# schematic_file.net
KiCad netlist of a schematic drawn in EAGLE
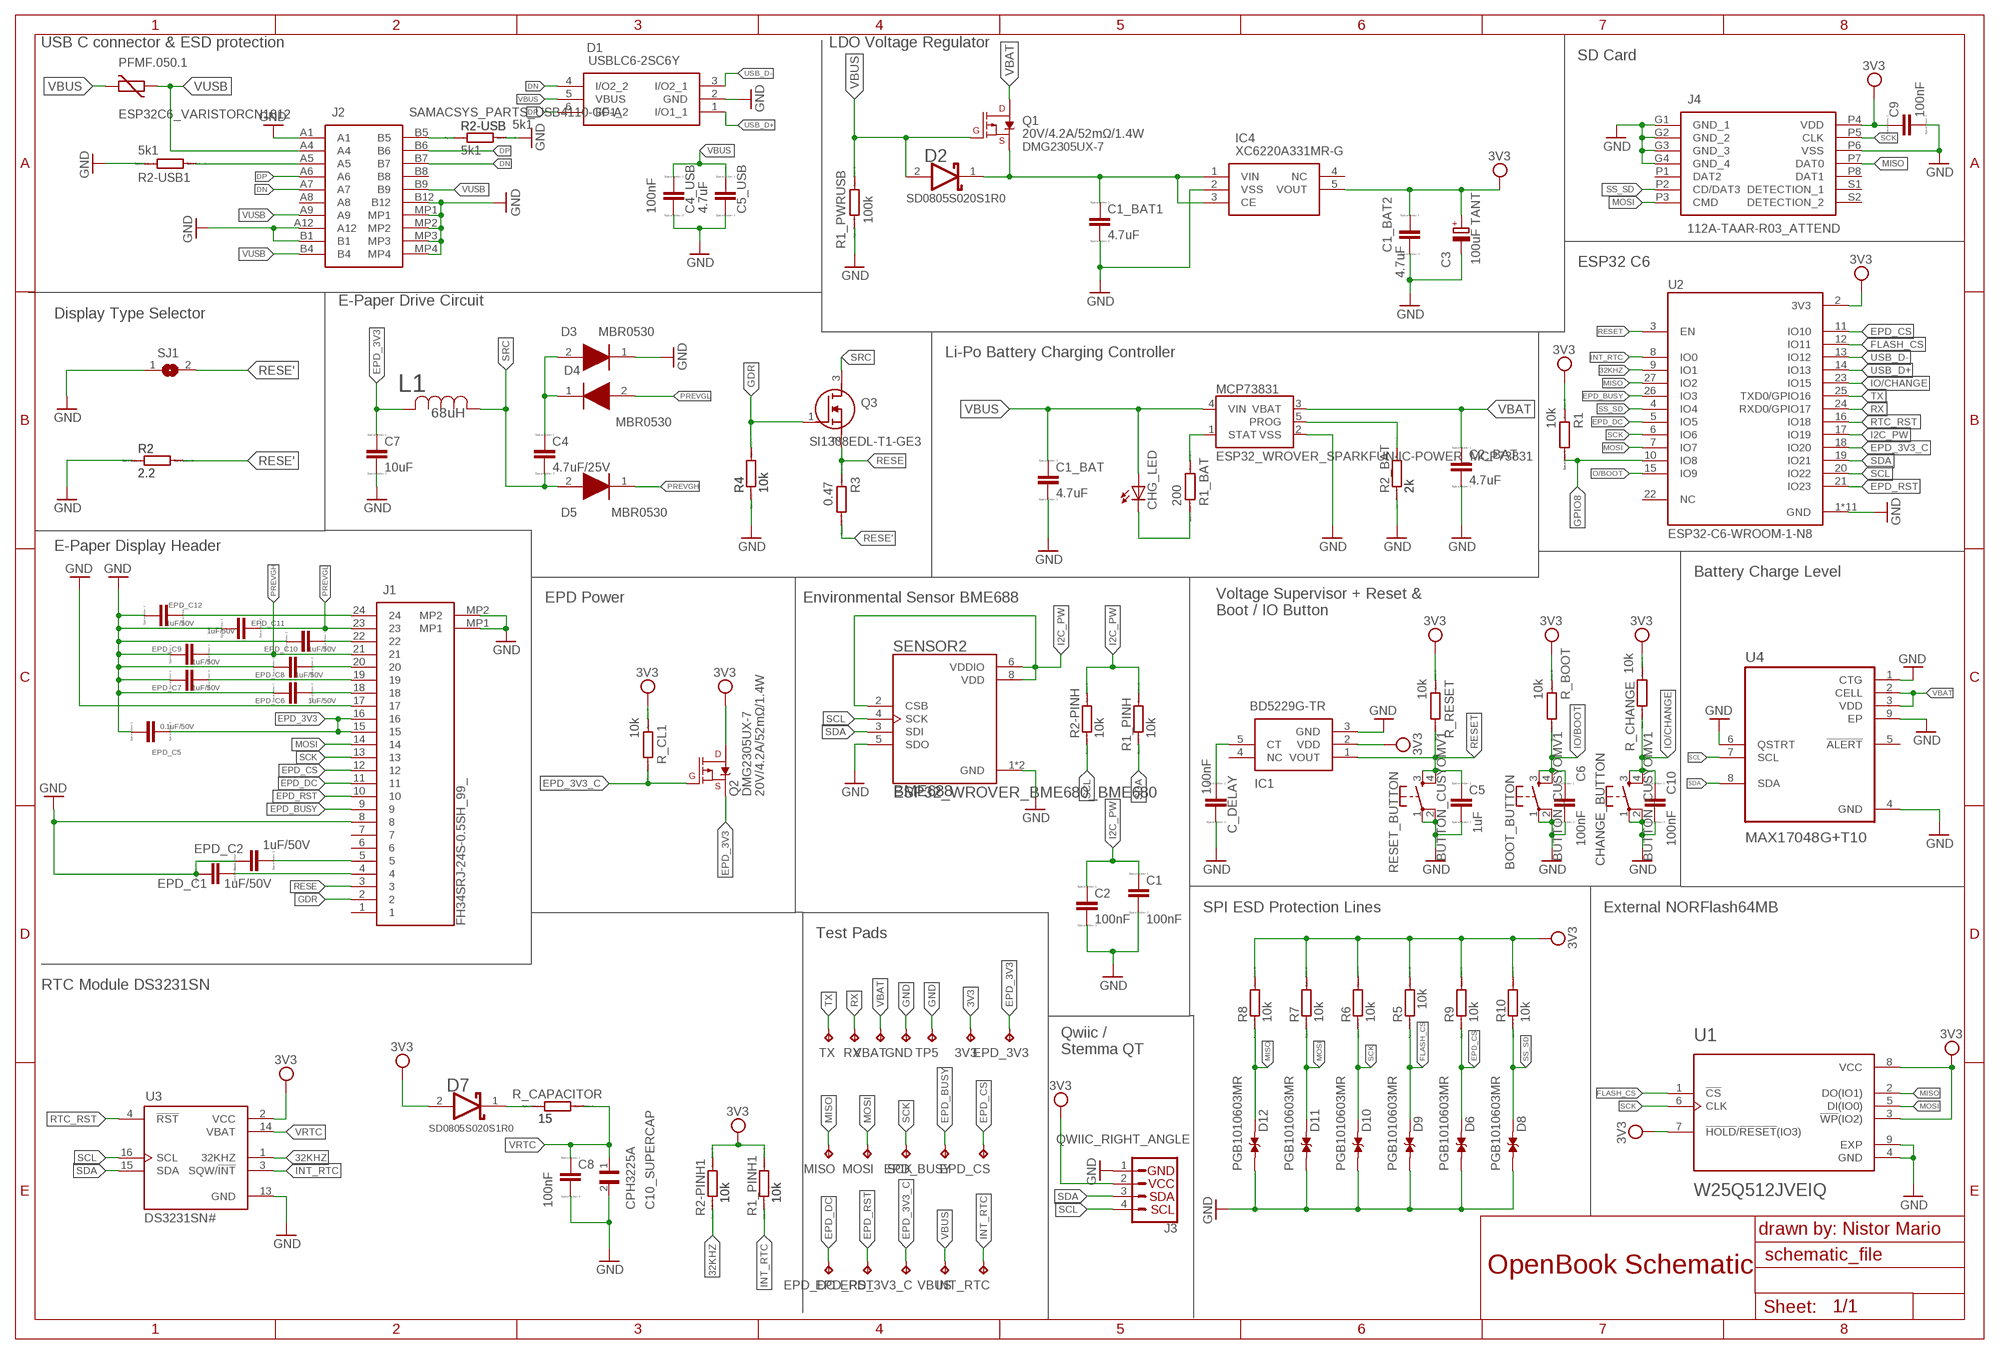
[diagram p0: schematic, sheet 1]

(export (version "E")
  (design (tool "Eeschema 10.0.6"))
  (components
    (comp (ref "3V3")
      (value "TPTP20R")
      (footprint "eagle-import:TP20R")
      (libsource (lib "eagle-import") (part "TPTP20R"))
    )
    (comp (ref "BOOT_BUTTON")
      (value "BUTTON_CUSYOMV1")
      (footprint "eagle-import:MYBUTTON")
      (libsource (lib "eagle-import") (part "BUTTON_CUSYOMV1"))
    )
    (comp (ref "C1")
      (value "100nF")
      (footprint "eagle-import:EAGLE-LTSPICE_C0402")
      (libsource (lib "eagle-import") (part "EAGLE-LTSPICE_CC0402"))
    )
    (comp (ref "C1_BAT")
      (value "4.7uF")
      (footprint "eagle-import:ESP32_WROVER_EAGLE-LTSPICE_C0402")
      (libsource (lib "eagle-import") (part "ESP32_WROVER_EAGLE-LTSPICE_CC0402"))
    )
    (comp (ref "C1_BAT1")
      (value "4.7uF")
      (footprint "eagle-import:EAGLE-LTSPICE_C0402")
      (libsource (lib "eagle-import") (part "EAGLE-LTSPICE_CC0402"))
    )
    (comp (ref "C1_BAT2")
      (value "4.7uF")
      (footprint "eagle-import:ESP32_WROVER_EAGLE-LTSPICE_C0402")
      (libsource (lib "eagle-import") (part "ESP32_WROVER_EAGLE-LTSPICE_CC0402"))
    )
    (comp (ref "C2")
      (value "100nF")
      (footprint "eagle-import:EAGLE-LTSPICE_C0402")
      (libsource (lib "eagle-import") (part "EAGLE-LTSPICE_CC0402"))
    )
    (comp (ref "C2_BAT")
      (value "4.7uF")
      (footprint "eagle-import:EAGLE-LTSPICE_C0402")
      (libsource (lib "eagle-import") (part "EAGLE-LTSPICE_CC0402"))
    )
    (comp (ref "C3")
      (value "100uF TANT")
      (footprint "eagle-import:RCL_CT3528")
      (libsource (lib "eagle-import") (part "RCL_CPOL-EUCT3528"))
    )
    (comp (ref "C4")
      (value "4.7uF/25V")
      (footprint "eagle-import:EAGLE-LTSPICE_C0402")
      (libsource (lib "eagle-import") (part "EAGLE-LTSPICE_CC0402"))
    )
    (comp (ref "C4_USB")
      (value "100nF")
      (footprint "eagle-import:ESP32_WROVER_EAGLE-LTSPICE_C0402")
      (libsource (lib "eagle-import") (part "ESP32_WROVER_EAGLE-LTSPICE_CC0402"))
    )
    (comp (ref "C5")
      (value "1uF")
      (footprint "eagle-import:EAGLE-LTSPICE_C0402")
      (libsource (lib "eagle-import") (part "EAGLE-LTSPICE_CC0402"))
    )
    (comp (ref "C5_USB")
      (value "4.7uF")
      (footprint "eagle-import:ESP32_WROVER_EAGLE-LTSPICE_C0402")
      (libsource (lib "eagle-import") (part "ESP32_WROVER_EAGLE-LTSPICE_CC0402"))
    )
    (comp (ref "C6")
      (value "100nF")
      (footprint "eagle-import:ESP32_WROVER_EAGLE-LTSPICE_C0402")
      (libsource (lib "eagle-import") (part "ESP32_WROVER_EAGLE-LTSPICE_CC0402"))
    )
    (comp (ref "C7")
      (value "10uF")
      (footprint "eagle-import:EAGLE-LTSPICE_C0402")
      (libsource (lib "eagle-import") (part "EAGLE-LTSPICE_CC0402"))
    )
    (comp (ref "C8")
      (value "100nF")
      (footprint "eagle-import:EAGLE-LTSPICE_C0402")
      (libsource (lib "eagle-import") (part "EAGLE-LTSPICE_CC0402"))
    )
    (comp (ref "C9")
      (value "100nF")
      (footprint "eagle-import:EAGLE-LTSPICE_C0402")
      (libsource (lib "eagle-import") (part "EAGLE-LTSPICE_CC0402"))
    )
    (comp (ref "C10")
      (value "100nF")
      (footprint "eagle-import:ESP32_WROVER_EAGLE-LTSPICE_C0402")
      (libsource (lib "eagle-import") (part "ESP32_WROVER_EAGLE-LTSPICE_CC0402"))
    )
    (comp (ref "C10_SUPERCAP")
      (value "CPH3225A")
      (footprint "eagle-import:CAPCP3225X100N")
      (fields (field (name "MF") "Seiko Instruments"))
      (libsource (lib "eagle-import") (part "CPH3225A"))
    )
    (comp (ref "CHANGE_BUTTON")
      (value "BUTTON_CUSYOMV1")
      (footprint "eagle-import:MYBUTTON")
      (libsource (lib "eagle-import") (part "BUTTON_CUSYOMV1"))
    )
    (comp (ref "CHG_LED")
      (value "ADAFRUIT_LEDCHIP-LED0603")
      (footprint "eagle-import:ADAFRUIT_CHIP-LED0603")
      (libsource (lib "eagle-import") (part "ADAFRUIT_LEDCHIP-LED0603"))
    )
    (comp (ref "C_DELAY")
      (value "100nF")
      (footprint "eagle-import:EAGLE-LTSPICE_C0402")
      (libsource (lib "eagle-import") (part "EAGLE-LTSPICE_CC0402"))
    )
    (comp (ref "D1")
      (value "USBLC6-2SC6Y")
      (footprint "eagle-import:SOT95P280X145-6N")
      (fields (field (name "MF") "STMicroelectronics"))
      (libsource (lib "eagle-import") (part "USBLC6-2SC6Y"))
    )
    (comp (ref "D2")
      (value "ESP32_WROVER_AVX---SD0805S020S1R0_AVX_SD0805S020S1R0_0_0AVX_SD0805S020S1R0_0_0")
      (footprint "eagle-import:ESP32_WROVER_AVX---SD0805S020S1R0_AVX_SD0805S020S1R0_0")
      (fields
        (field (name "DIGIKEY_PART_NUMBER") "478-7800-1-ND")
        (field (name "MF") "AVX")
        (field (name "MOUSER_PART_NUMBER") "581-SD0805S020S1R0")
      )
      (libsource (lib "eagle-import") (part "ESP32_WROVER_AVX---SD0805S020S1R0_AVX_SD0805S020S1R0_0_0AVX_SD0805S020S1R0_0_0"))
    )
    (comp (ref "D3")
      (value "MBR0530")
      (footprint "eagle-import:SOD3716X135N")
      (fields (field (name "MF") "ON Semiconductor"))
      (libsource (lib "eagle-import") (part "MBR0530"))
    )
    (comp (ref "D4")
      (value "MBR0530")
      (footprint "eagle-import:SOD3716X135N")
      (fields (field (name "MF") "ON Semiconductor"))
      (libsource (lib "eagle-import") (part "MBR0530"))
    )
    (comp (ref "D5")
      (value "MBR0530")
      (footprint "eagle-import:SOD3716X135N")
      (fields (field (name "MF") "ON Semiconductor"))
      (libsource (lib "eagle-import") (part "MBR0530"))
    )
    (comp (ref "D6")
      (value "PGB1010603MR")
      (footprint "eagle-import:DIOC1608X36N")
      (fields (field (name "MF") "Littelfuse Inc."))
      (libsource (lib "eagle-import") (part "PGB1010603MR"))
    )
    (comp (ref "D7")
      (value "ESP32_WROVER_AVX---SD0805S020S1R0_AVX_SD0805S020S1R0_0_0AVX_SD0805S020S1R0_0_0")
      (footprint "eagle-import:ESP32_WROVER_AVX---SD0805S020S1R0_AVX_SD0805S020S1R0_0")
      (fields
        (field (name "DIGIKEY_PART_NUMBER") "478-7800-1-ND")
        (field (name "MF") "AVX")
        (field (name "MOUSER_PART_NUMBER") "581-SD0805S020S1R0")
      )
      (libsource (lib "eagle-import") (part "ESP32_WROVER_AVX---SD0805S020S1R0_AVX_SD0805S020S1R0_0_0AVX_SD0805S020S1R0_0_0"))
    )
    (comp (ref "D8")
      (value "PGB1010603MR")
      (footprint "eagle-import:DIOC1608X36N")
      (fields (field (name "MF") "Littelfuse Inc."))
      (libsource (lib "eagle-import") (part "PGB1010603MR"))
    )
    (comp (ref "D9")
      (value "PGB1010603MR")
      (footprint "eagle-import:DIOC1608X36N")
      (fields (field (name "MF") "Littelfuse Inc."))
      (libsource (lib "eagle-import") (part "PGB1010603MR"))
    )
    (comp (ref "D10")
      (value "PGB1010603MR")
      (footprint "eagle-import:DIOC1608X36N")
      (fields (field (name "MF") "Littelfuse Inc."))
      (libsource (lib "eagle-import") (part "PGB1010603MR"))
    )
    (comp (ref "D11")
      (value "PGB1010603MR")
      (footprint "eagle-import:DIOC1608X36N")
      (fields (field (name "MF") "Littelfuse Inc."))
      (libsource (lib "eagle-import") (part "PGB1010603MR"))
    )
    (comp (ref "D12")
      (value "PGB1010603MR")
      (footprint "eagle-import:DIOC1608X36N")
      (fields (field (name "MF") "Littelfuse Inc."))
      (libsource (lib "eagle-import") (part "PGB1010603MR"))
    )
    (comp (ref "EPD_3V3")
      (value "TPTP20R")
      (footprint "eagle-import:TP20R")
      (libsource (lib "eagle-import") (part "TPTP20R"))
    )
    (comp (ref "EPD_3V3_C")
      (value "TPTP20R")
      (footprint "eagle-import:TP20R")
      (libsource (lib "eagle-import") (part "TPTP20R"))
    )
    (comp (ref "EPD_BUSY")
      (value "TPTP20R")
      (footprint "eagle-import:TP20R")
      (libsource (lib "eagle-import") (part "TPTP20R"))
    )
    (comp (ref "EPD_C1")
      (value "1uF/50V")
      (footprint "eagle-import:ESP32_WROVER_EAGLE-LTSPICE_C0402")
      (libsource (lib "eagle-import") (part "ESP32_WROVER_EAGLE-LTSPICE_CC0402"))
    )
    (comp (ref "EPD_C2")
      (value "1uF/50V")
      (footprint "eagle-import:ESP32_WROVER_EAGLE-LTSPICE_C0402")
      (libsource (lib "eagle-import") (part "ESP32_WROVER_EAGLE-LTSPICE_CC0402"))
    )
    (comp (ref "EPD_C5")
      (value "0.1uF/50V")
      (footprint "eagle-import:ESP32_WROVER_EAGLE-LTSPICE_C0402")
      (libsource (lib "eagle-import") (part "ESP32_WROVER_EAGLE-LTSPICE_CC0402"))
    )
    (comp (ref "EPD_C6")
      (value "1uF/50V")
      (footprint "eagle-import:ESP32_WROVER_EAGLE-LTSPICE_C0402")
      (libsource (lib "eagle-import") (part "ESP32_WROVER_EAGLE-LTSPICE_CC0402"))
    )
    (comp (ref "EPD_C7")
      (value "1uF/50V")
      (footprint "eagle-import:ESP32_WROVER_EAGLE-LTSPICE_C0402")
      (libsource (lib "eagle-import") (part "ESP32_WROVER_EAGLE-LTSPICE_CC0402"))
    )
    (comp (ref "EPD_C8")
      (value "1uF/50V")
      (footprint "eagle-import:ESP32_WROVER_EAGLE-LTSPICE_C0402")
      (libsource (lib "eagle-import") (part "ESP32_WROVER_EAGLE-LTSPICE_CC0402"))
    )
    (comp (ref "EPD_C9")
      (value "1uF/50V")
      (footprint "eagle-import:ESP32_WROVER_EAGLE-LTSPICE_C0402")
      (libsource (lib "eagle-import") (part "ESP32_WROVER_EAGLE-LTSPICE_CC0402"))
    )
    (comp (ref "EPD_C10")
      (value "1uF/50V")
      (footprint "eagle-import:ESP32_WROVER_EAGLE-LTSPICE_C0402")
      (libsource (lib "eagle-import") (part "ESP32_WROVER_EAGLE-LTSPICE_CC0402"))
    )
    (comp (ref "EPD_C11")
      (value "1uF/50V")
      (footprint "eagle-import:ESP32_WROVER_EAGLE-LTSPICE_C0402")
      (libsource (lib "eagle-import") (part "ESP32_WROVER_EAGLE-LTSPICE_CC0402"))
    )
    (comp (ref "EPD_C12")
      (value "1uF/50V")
      (footprint "eagle-import:ESP32_WROVER_EAGLE-LTSPICE_C0402")
      (libsource (lib "eagle-import") (part "ESP32_WROVER_EAGLE-LTSPICE_CC0402"))
    )
    (comp (ref "EPD_CS")
      (value "TPTP20R")
      (footprint "eagle-import:TP20R")
      (libsource (lib "eagle-import") (part "TPTP20R"))
    )
    (comp (ref "EPD_DC")
      (value "TPTP20R")
      (footprint "eagle-import:TP20R")
      (libsource (lib "eagle-import") (part "TPTP20R"))
    )
    (comp (ref "EPD_RST")
      (value "TPTP20R")
      (footprint "eagle-import:TP20R")
      (libsource (lib "eagle-import") (part "TPTP20R"))
    )
    (comp (ref "GND")
      (value "TPTP20R")
      (footprint "eagle-import:TP20R")
      (libsource (lib "eagle-import") (part "TPTP20R"))
    )
    (comp (ref "IC1")
      (value "BD5229G-TR")
      (footprint "eagle-import:SOT95P280X125-5N")
      (fields (field (name "MOUSER_PART_NUMBER") "755-BD5229G-TR"))
      (libsource (lib "eagle-import") (part "BD5229G-TR"))
    )
    (comp (ref "IC4")
      (value "XC6220A331MR-G")
      (footprint "eagle-import:SOT95P280X120-5N")
      (fields (field (name "MOUSER_PART_NUMBER") "865-XC6220A331MR-G"))
      (libsource (lib "eagle-import") (part "XC6220A331MR-G"))
    )
    (comp (ref "INT_RTC")
      (value "TPTP20R")
      (footprint "eagle-import:TP20R")
      (libsource (lib "eagle-import") (part "TPTP20R"))
    )
    (comp (ref "J1")
      (value "FH34SRJ-24S-0.5SH_99_")
      (footprint "eagle-import:FH34SRJ24S05SH99")
      (fields
        (field (name "MANUFACTURER_PART_NUMBER") "FH34SRJ-24S-0.5SH(99)")
        (field (name "MOUSER_PART_NUMBER") "798-FH34SRJ24S05SH99")
      )
      (libsource (lib "eagle-import") (part "FH34SRJ-24S-0.5SH_99_"))
    )
    (comp (ref "J2")
      (value "SAMACSYS_PARTS_USB4110-GF-A")
      (footprint "eagle-import:SAMACSYS_PARTS_USB4110GFA")
      (fields
        (field (name "MANUFACTURER_PART_NUMBER") "USB4110-GF-A")
        (field (name "MOUSER_PART_NUMBER") "640-USB4110-GF-A")
      )
      (libsource (lib "eagle-import") (part "SAMACSYS_PARTS_USB4110-GF-A"))
    )
    (comp (ref "J3")
      (value "QWIIC_RIGHT_ANGLE")
      (footprint "eagle-import:JST04_1MM_RA")
      (libsource (lib "eagle-import") (part "QWIIC_CONNECTORJS-1MM"))
    )
    (comp (ref "J4")
      (value "112A-TAAR-R03_ATTEND")
      (footprint "eagle-import:112ATAARR03ATTEND")
      (fields (field (name "MANUFACTURER_PART_NUMBER") "112A-TAAR-R03 ATTEND"))
      (libsource (lib "eagle-import") (part "112A-TAAR-R03_ATTEND"))
    )
    (comp (ref "L1")
      (value "68uH")
      (footprint "eagle-import:IND_4828-WE-TPC_WRE")
      (fields
        (field (name "MANUFACTURER_PART_NUMBER") "744043680")
        (field (name "COPYRIGHT") "Copyright (C) 2024 Ultra Librarian. All rights reserved.")
      )
      (libsource (lib "eagle-import") (part "744043680IND_4828-WE-TPC_WRE"))
    )
    (comp (ref "MCP73831")
      (value "ESP32_WROVER_SPARKFUN-IC-POWER_MCP73831")
      (footprint "eagle-import:ESP32_WROVER_SPARKFUN-IC-POWER_SOT23-5")
      (libsource (lib "eagle-import") (part "ESP32_WROVER_SPARKFUN-IC-POWER_MCP73831"))
    )
    (comp (ref "MISO")
      (value "TPTP20R")
      (footprint "eagle-import:TP20R")
      (libsource (lib "eagle-import") (part "TPTP20R"))
    )
    (comp (ref "MOSI")
      (value "TPTP20R")
      (footprint "eagle-import:TP20R")
      (libsource (lib "eagle-import") (part "TPTP20R"))
    )
    (comp (ref "PFMF.050.1")
      (value "ESP32C6_VARISTORCN1812")
      (footprint "eagle-import:ESP32C6_VARISTOR_CT_CN1812")
      (libsource (lib "eagle-import") (part "ESP32C6_VARISTORCN1812"))
    )
    (comp (ref "Q1")
      (value "20V/4.2A/52mΩ/1.4W")
      (footprint "eagle-import:ESP32_WROVER_SPARKFUN-DISCRETESEMI_SOT23-3")
      (libsource (lib "eagle-import") (part "ESP32_WROVER_SPARKFUN-DISCRETESEMI_MOSFET_PCH-DMG2305UX-7"))
    )
    (comp (ref "Q2")
      (value "20V/4.2A/52mΩ/1.4W")
      (footprint "eagle-import:ESP32_WROVER_SPARKFUN-DISCRETESEMI_SOT23-3")
      (libsource (lib "eagle-import") (part "ESP32_WROVER_SPARKFUN-DISCRETESEMI_MOSFET_PCH-DMG2305UX-7"))
    )
    (comp (ref "Q3")
      (value "SI1308EDL-T1-GE3")
      (footprint "eagle-import:SOT65P210X110-3N")
      (fields (field (name "MF") "Vishay Siliconix"))
      (libsource (lib "eagle-import") (part "SI1308EDL-T1-GE3"))
    )
    (comp (ref "R1")
      (value "10k")
      (footprint "eagle-import:ESP32_WROVER_EAGLE-LTSPICE_R0402")
      (libsource (lib "eagle-import") (part "ESP32_WROVER_EAGLE-LTSPICE_RR0402"))
    )
    (comp (ref "R1_BAT")
      (value "200")
      (footprint "eagle-import:ESP32_WROVER_EAGLE-LTSPICE_R0402")
      (libsource (lib "eagle-import") (part "ESP32_WROVER_EAGLE-LTSPICE_RR0402"))
    )
    (comp (ref "R1_PINH")
      (value "10k")
      (footprint "eagle-import:ESP32_WROVER_EAGLE-LTSPICE_R0402")
      (libsource (lib "eagle-import") (part "ESP32_WROVER_EAGLE-LTSPICE_RR0402"))
    )
    (comp (ref "R1_PINH1")
      (value "10k")
      (footprint "eagle-import:ESP32_WROVER_EAGLE-LTSPICE_R0402")
      (libsource (lib "eagle-import") (part "ESP32_WROVER_EAGLE-LTSPICE_RR0402"))
    )
    (comp (ref "R1_PWRUSB")
      (value "100k")
      (footprint "eagle-import:ESP32_WROVER_EAGLE-LTSPICE_R0402")
      (libsource (lib "eagle-import") (part "ESP32_WROVER_EAGLE-LTSPICE_RR0402"))
    )
    (comp (ref "R2")
      (value "2.2")
      (footprint "eagle-import:ESP32_WROVER_EAGLE-LTSPICE_R0402")
      (libsource (lib "eagle-import") (part "ESP32_WROVER_EAGLE-LTSPICE_RR0402"))
    )
    (comp (ref "R2-PINH")
      (value "10k")
      (footprint "eagle-import:ESP32_WROVER_EAGLE-LTSPICE_R0402")
      (libsource (lib "eagle-import") (part "ESP32_WROVER_EAGLE-LTSPICE_RR0402"))
    )
    (comp (ref "R2-PINH1")
      (value "10k")
      (footprint "eagle-import:ESP32_WROVER_EAGLE-LTSPICE_R0402")
      (libsource (lib "eagle-import") (part "ESP32_WROVER_EAGLE-LTSPICE_RR0402"))
    )
    (comp (ref "R2-USB")
      (value "5k1")
      (footprint "eagle-import:ESP32_WROVER_EAGLE-LTSPICE_R0402")
      (libsource (lib "eagle-import") (part "ESP32_WROVER_EAGLE-LTSPICE_RR0402"))
    )
    (comp (ref "R2-USB1")
      (value "5k1")
      (footprint "eagle-import:ESP32_WROVER_EAGLE-LTSPICE_R0402")
      (libsource (lib "eagle-import") (part "ESP32_WROVER_EAGLE-LTSPICE_RR0402"))
    )
    (comp (ref "R2_BAT")
      (value "2k")
      (footprint "eagle-import:ESP32_WROVER_EAGLE-LTSPICE_R0402")
      (libsource (lib "eagle-import") (part "ESP32_WROVER_EAGLE-LTSPICE_RR0402"))
    )
    (comp (ref "R3")
      (value "0.47")
      (footprint "eagle-import:ESP32_WROVER_EAGLE-LTSPICE_R0402")
      (libsource (lib "eagle-import") (part "ESP32_WROVER_EAGLE-LTSPICE_RR0402"))
    )
    (comp (ref "R4")
      (value "10k")
      (footprint "eagle-import:ESP32_WROVER_EAGLE-LTSPICE_R0402")
      (libsource (lib "eagle-import") (part "ESP32_WROVER_EAGLE-LTSPICE_RR0402"))
    )
    (comp (ref "R5")
      (value "10k")
      (footprint "eagle-import:ESP32_WROVER_EAGLE-LTSPICE_R0402")
      (libsource (lib "eagle-import") (part "ESP32_WROVER_EAGLE-LTSPICE_RR0402"))
    )
    (comp (ref "R6")
      (value "10k")
      (footprint "eagle-import:ESP32_WROVER_EAGLE-LTSPICE_R0402")
      (libsource (lib "eagle-import") (part "ESP32_WROVER_EAGLE-LTSPICE_RR0402"))
    )
    (comp (ref "R7")
      (value "10k")
      (footprint "eagle-import:ESP32_WROVER_EAGLE-LTSPICE_R0402")
      (libsource (lib "eagle-import") (part "ESP32_WROVER_EAGLE-LTSPICE_RR0402"))
    )
    (comp (ref "R8")
      (value "10k")
      (footprint "eagle-import:ESP32_WROVER_EAGLE-LTSPICE_R0402")
      (libsource (lib "eagle-import") (part "ESP32_WROVER_EAGLE-LTSPICE_RR0402"))
    )
    (comp (ref "R9")
      (value "10k")
      (footprint "eagle-import:ESP32_WROVER_EAGLE-LTSPICE_R0402")
      (libsource (lib "eagle-import") (part "ESP32_WROVER_EAGLE-LTSPICE_RR0402"))
    )
    (comp (ref "R10")
      (value "10k")
      (footprint "eagle-import:ESP32_WROVER_EAGLE-LTSPICE_R0402")
      (libsource (lib "eagle-import") (part "ESP32_WROVER_EAGLE-LTSPICE_RR0402"))
    )
    (comp (ref "RESET_BUTTON")
      (value "BUTTON_CUSYOMV1")
      (footprint "eagle-import:MYBUTTON")
      (libsource (lib "eagle-import") (part "BUTTON_CUSYOMV1"))
    )
    (comp (ref "RX")
      (value "TPTP20R")
      (footprint "eagle-import:TP20R")
      (libsource (lib "eagle-import") (part "TPTP20R"))
    )
    (comp (ref "R_BOOT")
      (value "10k")
      (footprint "eagle-import:ESP32_WROVER_EAGLE-LTSPICE_R0402")
      (libsource (lib "eagle-import") (part "ESP32_WROVER_EAGLE-LTSPICE_RR0402"))
    )
    (comp (ref "R_CAPACITOR")
      (value "15")
      (footprint "eagle-import:ESP32_WROVER_EAGLE-LTSPICE_R0402")
      (libsource (lib "eagle-import") (part "ESP32_WROVER_EAGLE-LTSPICE_RR0402"))
    )
    (comp (ref "R_CHANGE")
      (value "10k")
      (footprint "eagle-import:ESP32_WROVER_EAGLE-LTSPICE_R0402")
      (libsource (lib "eagle-import") (part "ESP32_WROVER_EAGLE-LTSPICE_RR0402"))
    )
    (comp (ref "R_CL1")
      (value "10k")
      (footprint "eagle-import:ESP32_WROVER_EAGLE-LTSPICE_R0402")
      (libsource (lib "eagle-import") (part "ESP32_WROVER_EAGLE-LTSPICE_RR0402"))
    )
    (comp (ref "R_RESET")
      (value "10k")
      (footprint "eagle-import:ESP32_WROVER_EAGLE-LTSPICE_R0402")
      (libsource (lib "eagle-import") (part "ESP32_WROVER_EAGLE-LTSPICE_RR0402"))
    )
    (comp (ref "SCK")
      (value "TPTP20R")
      (footprint "eagle-import:TP20R")
      (libsource (lib "eagle-import") (part "TPTP20R"))
    )
    (comp (ref "SENSOR2")
      (value "ESP32_WROVER_BME680_BME680")
      (footprint "eagle-import:ESP32_WROVER_BME680_PSON80P300X300X100-8N")
      (fields (field (name "MF") "Bosch Sensortec") (field (name "MP") "BME680"))
      (libsource (lib "eagle-import") (part "ESP32_WROVER_BME680_BME680"))
    )
    (comp (ref "SJ1") (value "SJ") (footprint "eagle-import:SJ") (libsource (lib "eagle-import") (part "SJ")))
    (comp (ref "TP5")
      (value "TPTP20R")
      (footprint "eagle-import:TP20R")
      (libsource (lib "eagle-import") (part "TPTP20R"))
    )
    (comp (ref "TX")
      (value "TPTP20R")
      (footprint "eagle-import:TP20R")
      (libsource (lib "eagle-import") (part "TPTP20R"))
    )
    (comp (ref "U1")
      (value "W25Q512JVEIQ")
      (footprint "eagle-import:SON127P600X800X80-9N")
      (fields (field (name "MF") "Winbond Electronics"))
      (libsource (lib "eagle-import") (part "W25Q512JVEIQ"))
    )
    (comp (ref "U2")
      (value "ESP32-C6-WROOM-1-N8")
      (footprint "eagle-import:XCVR_ESP32-C6-WROOM-1-N8")
      (fields (field (name "MF") "Espressif Systems"))
      (libsource (lib "eagle-import") (part "ESP32-C6-WROOM-1-N8"))
    )
    (comp (ref "U3")
      (value "DS3231SN#")
      (footprint "eagle-import:SOIC127P1032X265-16N")
      (fields (field (name "MF") "Analog Devices"))
      (libsource (lib "eagle-import") (part "DS3231SN#"))
    )
    (comp (ref "U4")
      (value "MAX17048G+T10")
      (footprint "eagle-import:SON50P200X200X80-9N")
      (fields (field (name "MF") "Analog Devices"))
      (libsource (lib "eagle-import") (part "MAX17048G+T10"))
    )
    (comp (ref "VBAT")
      (value "TPTP20R")
      (footprint "eagle-import:TP20R")
      (libsource (lib "eagle-import") (part "TPTP20R"))
    )
    (comp (ref "VBUS")
      (value "TPTP20R")
      (footprint "eagle-import:TP20R")
      (libsource (lib "eagle-import") (part "TPTP20R"))
    )
  )
  (nets
    (net (code "1") (name "3V3") (class "Default")
      (node (ref "3V3") (pin "TP") (pinfunction "TP_TP") (pintype "input"))
      (node (ref "C1_BAT2") (pin "1") (pinfunction "1_1") (pintype "passive"))
      (node (ref "C3") (pin "+") (pinfunction "+_+") (pintype "passive"))
      (node (ref "C9") (pin "1") (pinfunction "1_1") (pintype "passive"))
      (node (ref "D7") (pin "2") (pinfunction "ANODE_2") (pintype "bidirectional"))
      (node (ref "IC1") (pin "2") (pinfunction "VDD_2") (pintype "bidirectional"))
      (node (ref "IC4") (pin "5") (pinfunction "VOUT_5") (pintype "bidirectional"))
      (node (ref "J3") (pin "2") (pinfunction "2_2") (pintype "power_in"))
      (node (ref "J4") (pin "P4") (pinfunction "VDD_P4") (pintype "bidirectional"))
      (node (ref "Q2") (pin "3") (pinfunction "D_3") (pintype "bidirectional"))
      (node (ref "R1") (pin "2") (pinfunction "2_2") (pintype "passive"))
      (node (ref "R10") (pin "2") (pinfunction "2_2") (pintype "passive"))
      (node (ref "R1_PINH1") (pin "2") (pinfunction "2_2") (pintype "passive"))
      (node (ref "R2-PINH1") (pin "2") (pinfunction "2_2") (pintype "passive"))
      (node (ref "R5") (pin "2") (pinfunction "2_2") (pintype "passive"))
      (node (ref "R6") (pin "2") (pinfunction "2_2") (pintype "passive"))
      (node (ref "R7") (pin "2") (pinfunction "2_2") (pintype "passive"))
      (node (ref "R8") (pin "2") (pinfunction "2_2") (pintype "passive"))
      (node (ref "R9") (pin "2") (pinfunction "2_2") (pintype "passive"))
      (node (ref "R_BOOT") (pin "2") (pinfunction "2_2") (pintype "passive"))
      (node (ref "R_CHANGE") (pin "2") (pinfunction "2_2") (pintype "passive"))
      (node (ref "R_CL1") (pin "2") (pinfunction "2_2") (pintype "passive"))
      (node (ref "R_RESET") (pin "2") (pinfunction "2_2") (pintype "passive"))
      (node (ref "U1") (pin "3") (pinfunction "~{WP}(IO2)_3") (pintype "bidirectional"))
      (node (ref "U1") (pin "7") (pinfunction "~{HOLD}/~{RESET}(IO3)_7") (pintype "bidirectional"))
      (node (ref "U1") (pin "8") (pinfunction "VCC_8") (pintype "power_in"))
      (node (ref "U2") (pin "2") (pinfunction "3V3_2") (pintype "power_in"))
      (node (ref "U3") (pin "2") (pinfunction "VCC_2") (pintype "power_in"))
    )
    (net (code "2") (name "32KHZ") (class "Default")
      (node (ref "R2-PINH1") (pin "1") (pinfunction "1_1") (pintype "passive"))
      (node (ref "U2") (pin "9") (pinfunction "IO1_9") (pintype "bidirectional"))
      (node (ref "U3") (pin "1") (pinfunction "32KHZ_1") (pintype "output"))
    )
    (net (code "3") (name "DN") (class "Default")
      (node (ref "D1") (pin "4") (pinfunction "I/O2_2_4") (pintype "bidirectional"))
      (node (ref "J2") (pin "A7") (pinfunction "A7_A7") (pintype "bidirectional"))
      (node (ref "J2") (pin "B7") (pinfunction "B7_B7") (pintype "bidirectional"))
    )
    (net (code "4") (name "DP") (class "Default")
      (node (ref "D1") (pin "6") (pinfunction "I/O1_2_6") (pintype "bidirectional"))
      (node (ref "J2") (pin "A6") (pinfunction "A6_A6") (pintype "bidirectional"))
      (node (ref "J2") (pin "B6") (pinfunction "B6_B6") (pintype "bidirectional"))
    )
    (net (code "5") (name "EPD_3V3") (class "Default")
      (node (ref "C7") (pin "1") (pinfunction "1_1") (pintype "passive"))
      (node (ref "EPD_3V3") (pin "TP") (pinfunction "TP_TP") (pintype "input"))
      (node (ref "EPD_C5") (pin "2") (pinfunction "2_2") (pintype "passive"))
      (node (ref "J1") (pin "15") (pinfunction "15_15") (pintype "bidirectional"))
      (node (ref "J1") (pin "16") (pinfunction "16_16") (pintype "bidirectional"))
      (node (ref "L1") (pin "2") (pinfunction "2_2") (pintype "passive"))
      (node (ref "Q2") (pin "2") (pinfunction "S_2") (pintype "bidirectional"))
    )
    (net (code "6") (name "EPD_3V3_C") (class "Default")
      (node (ref "EPD_3V3_C") (pin "TP") (pinfunction "TP_TP") (pintype "input"))
      (node (ref "Q2") (pin "1") (pinfunction "G_1") (pintype "bidirectional"))
      (node (ref "R_CL1") (pin "1") (pinfunction "1_1") (pintype "passive"))
      (node (ref "U2") (pin "18") (pinfunction "IO20_18") (pintype "bidirectional"))
    )
    (net (code "7") (name "EPD_BUSY") (class "Default")
      (node (ref "EPD_BUSY") (pin "TP") (pinfunction "TP_TP") (pintype "input"))
      (node (ref "J1") (pin "9") (pinfunction "9_9") (pintype "bidirectional"))
      (node (ref "U2") (pin "26") (pinfunction "IO3_26") (pintype "bidirectional"))
    )
    (net (code "8") (name "EPD_CS") (class "Default")
      (node (ref "D6") (pin "2") (pinfunction "2_2") (pintype "passive"))
      (node (ref "EPD_CS") (pin "TP") (pinfunction "TP_TP") (pintype "input"))
      (node (ref "J1") (pin "12") (pinfunction "12_12") (pintype "bidirectional"))
      (node (ref "R9") (pin "1") (pinfunction "1_1") (pintype "passive"))
      (node (ref "U2") (pin "11") (pinfunction "IO10_11") (pintype "bidirectional"))
    )
    (net (code "9") (name "EPD_DC") (class "Default")
      (node (ref "EPD_DC") (pin "TP") (pinfunction "TP_TP") (pintype "input"))
      (node (ref "J1") (pin "11") (pinfunction "11_11") (pintype "bidirectional"))
      (node (ref "U2") (pin "5") (pinfunction "IO5_5") (pintype "bidirectional"))
    )
    (net (code "10") (name "EPD_RST") (class "Default")
      (node (ref "EPD_RST") (pin "TP") (pinfunction "TP_TP") (pintype "input"))
      (node (ref "J1") (pin "10") (pinfunction "10_10") (pintype "bidirectional"))
      (node (ref "U2") (pin "21") (pinfunction "IO23_21") (pintype "bidirectional"))
    )
    (net (code "11") (name "FLASH_CS") (class "Default")
      (node (ref "D9") (pin "2") (pinfunction "2_2") (pintype "passive"))
      (node (ref "R5") (pin "1") (pinfunction "1_1") (pintype "passive"))
      (node (ref "U1") (pin "1") (pinfunction "~{CS}_1") (pintype "input"))
      (node (ref "U2") (pin "12") (pinfunction "IO11_12") (pintype "bidirectional"))
    )
    (net (code "12") (name "GDR") (class "Default")
      (node (ref "J1") (pin "2") (pinfunction "2_2") (pintype "bidirectional"))
      (node (ref "Q3") (pin "1") (pinfunction "G_1") (pintype "bidirectional"))
      (node (ref "R4") (pin "2") (pinfunction "2_2") (pintype "passive"))
    )
    (net (code "13") (name "GND") (class "Default")
      (node (ref "BOOT_BUTTON") (pin "1") (pinfunction "1_1") (pintype "passive"))
      (node (ref "BOOT_BUTTON") (pin "2") (pinfunction "2_2") (pintype "passive"))
      (node (ref "C1") (pin "2") (pinfunction "2_2") (pintype "passive"))
      (node (ref "C10") (pin "2") (pinfunction "2_2") (pintype "passive"))
      (node (ref "C10_SUPERCAP") (pin "2") (pinfunction "2_2") (pintype "passive"))
      (node (ref "C1_BAT") (pin "2") (pinfunction "2_2") (pintype "passive"))
      (node (ref "C1_BAT1") (pin "2") (pinfunction "2_2") (pintype "passive"))
      (node (ref "C1_BAT2") (pin "2") (pinfunction "2_2") (pintype "passive"))
      (node (ref "C2") (pin "2") (pinfunction "2_2") (pintype "passive"))
      (node (ref "C2_BAT") (pin "2") (pinfunction "2_2") (pintype "passive"))
      (node (ref "C3") (pin "-") (pinfunction "-_-") (pintype "passive"))
      (node (ref "C4_USB") (pin "2") (pinfunction "2_2") (pintype "passive"))
      (node (ref "C5") (pin "2") (pinfunction "2_2") (pintype "passive"))
      (node (ref "C5_USB") (pin "2") (pinfunction "2_2") (pintype "passive"))
      (node (ref "C6") (pin "2") (pinfunction "2_2") (pintype "passive"))
      (node (ref "C7") (pin "2") (pinfunction "2_2") (pintype "passive"))
      (node (ref "C8") (pin "2") (pinfunction "2_2") (pintype "passive"))
      (node (ref "C9") (pin "2") (pinfunction "2_2") (pintype "passive"))
      (node (ref "CHANGE_BUTTON") (pin "1") (pinfunction "1_1") (pintype "passive"))
      (node (ref "CHANGE_BUTTON") (pin "2") (pinfunction "2_2") (pintype "passive"))
      (node (ref "C_DELAY") (pin "2") (pinfunction "2_2") (pintype "passive"))
      (node (ref "D1") (pin "2") (pinfunction "GND_2") (pintype "bidirectional"))
      (node (ref "D10") (pin "1") (pinfunction "1_1") (pintype "passive"))
      (node (ref "D11") (pin "1") (pinfunction "1_1") (pintype "passive"))
      (node (ref "D12") (pin "1") (pinfunction "1_1") (pintype "passive"))
      (node (ref "D3") (pin "1") (pinfunction "K_1") (pintype "bidirectional"))
      (node (ref "D6") (pin "1") (pinfunction "1_1") (pintype "passive"))
      (node (ref "D8") (pin "1") (pinfunction "1_1") (pintype "passive"))
      (node (ref "D9") (pin "1") (pinfunction "1_1") (pintype "passive"))
      (node (ref "EPD_C1") (pin "1") (pinfunction "1_1") (pintype "passive"))
      (node (ref "EPD_C10") (pin "1") (pinfunction "1_1") (pintype "passive"))
      (node (ref "EPD_C11") (pin "1") (pinfunction "1_1") (pintype "passive"))
      (node (ref "EPD_C12") (pin "1") (pinfunction "1_1") (pintype "passive"))
      (node (ref "EPD_C2") (pin "1") (pinfunction "1_1") (pintype "passive"))
      (node (ref "EPD_C5") (pin "1") (pinfunction "1_1") (pintype "passive"))
      (node (ref "EPD_C6") (pin "1") (pinfunction "1_1") (pintype "passive"))
      (node (ref "EPD_C7") (pin "1") (pinfunction "1_1") (pintype "passive"))
      (node (ref "EPD_C8") (pin "1") (pinfunction "1_1") (pintype "passive"))
      (node (ref "EPD_C9") (pin "1") (pinfunction "1_1") (pintype "passive"))
      (node (ref "GND") (pin "TP") (pinfunction "TP_TP") (pintype "input"))
      (node (ref "IC1") (pin "3") (pinfunction "GND_3") (pintype "bidirectional"))
      (node (ref "IC4") (pin "2") (pinfunction "VSS_2") (pintype "bidirectional"))
      (node (ref "J1") (pin "17") (pinfunction "17_17") (pintype "bidirectional"))
      (node (ref "J1") (pin "8") (pinfunction "8_8") (pintype "bidirectional"))
      (node (ref "J1") (pin "MP1") (pinfunction "MP1_MP1") (pintype "bidirectional"))
      (node (ref "J1") (pin "MP2") (pinfunction "MP2_MP2") (pintype "bidirectional"))
      (node (ref "J2") (pin "A1") (pinfunction "A1_A1") (pintype "bidirectional"))
      (node (ref "J2") (pin "A12") (pinfunction "A12_A12") (pintype "bidirectional"))
      (node (ref "J2") (pin "B1") (pinfunction "B1_B1") (pintype "bidirectional"))
      (node (ref "J2") (pin "B12") (pinfunction "B12_B12") (pintype "bidirectional"))
      (node (ref "J2") (pin "MP1") (pinfunction "MP1_MP1") (pintype "bidirectional"))
      (node (ref "J2") (pin "MP2") (pinfunction "MP2_MP2") (pintype "bidirectional"))
      (node (ref "J2") (pin "MP3") (pinfunction "MP3_MP3") (pintype "bidirectional"))
      (node (ref "J2") (pin "MP4") (pinfunction "MP4_MP4") (pintype "bidirectional"))
      (node (ref "J3") (pin "1") (pinfunction "1_1") (pintype "power_in"))
      (node (ref "J4") (pin "G1") (pinfunction "GND_1_G1") (pintype "bidirectional"))
      (node (ref "J4") (pin "G2") (pinfunction "GND_2_G2") (pintype "bidirectional"))
      (node (ref "J4") (pin "G3") (pinfunction "GND_3_G3") (pintype "bidirectional"))
      (node (ref "J4") (pin "G4") (pinfunction "GND_4_G4") (pintype "bidirectional"))
      (node (ref "J4") (pin "P6") (pinfunction "VSS_P6") (pintype "bidirectional"))
      (node (ref "MCP73831") (pin "2") (pinfunction "VSS_2") (pintype "power_in"))
      (node (ref "R1_PWRUSB") (pin "2") (pinfunction "2_2") (pintype "passive"))
      (node (ref "R2") (pin "1") (pinfunction "1_1") (pintype "passive"))
      (node (ref "R2-USB") (pin "2") (pinfunction "2_2") (pintype "passive"))
      (node (ref "R2-USB1") (pin "1") (pinfunction "1_1") (pintype "passive"))
      (node (ref "R2_BAT") (pin "1") (pinfunction "1_1") (pintype "passive"))
      (node (ref "R4") (pin "1") (pinfunction "1_1") (pintype "passive"))
      (node (ref "RESET_BUTTON") (pin "1") (pinfunction "1_1") (pintype "passive"))
      (node (ref "RESET_BUTTON") (pin "2") (pinfunction "2_2") (pintype "passive"))
      (node (ref "SENSOR2") (pin "1") (pinfunction "GND_1") (pintype "power_in"))
      (node (ref "SENSOR2") (pin "5") (pinfunction "SDO_5") (pintype "bidirectional"))
      (node (ref "SENSOR2") (pin "7") (pinfunction "GND_7") (pintype "power_in"))
      (node (ref "SJ1") (pin "1") (pinfunction "1_1") (pintype "passive"))
      (node (ref "TP5") (pin "TP") (pinfunction "TP_TP") (pintype "input"))
      (node (ref "U1") (pin "4") (pinfunction "GND_4") (pintype "power_in"))
      (node (ref "U1") (pin "9") (pinfunction "EXP_9") (pintype "passive"))
      (node (ref "U2") (pin "1") (pinfunction "GND_1") (pintype "power_in"))
      (node (ref "U2") (pin "28") (pinfunction "GND_28") (pintype "power_in"))
      (node (ref "U2") (pin "29_1") (pinfunction "GND_29_1") (pintype "power_in"))
      (node (ref "U2") (pin "29_2") (pinfunction "GND_29_2") (pintype "power_in"))
      (node (ref "U2") (pin "29_3") (pinfunction "GND_29_3") (pintype "power_in"))
      (node (ref "U2") (pin "29_4") (pinfunction "GND_29_4") (pintype "power_in"))
      (node (ref "U2") (pin "29_5") (pinfunction "GND_29_5") (pintype "power_in"))
      (node (ref "U2") (pin "29_6") (pinfunction "GND_29_6") (pintype "power_in"))
      (node (ref "U2") (pin "29_7") (pinfunction "GND_29_7") (pintype "power_in"))
      (node (ref "U2") (pin "29_8") (pinfunction "GND_29_8") (pintype "power_in"))
      (node (ref "U2") (pin "29_9") (pinfunction "GND_29_9") (pintype "power_in"))
      (node (ref "U3") (pin "13") (pinfunction "GND_13") (pintype "power_in"))
      (node (ref "U4") (pin "1") (pinfunction "CTG_1") (pintype "power_in"))
      (node (ref "U4") (pin "4") (pinfunction "GND_4") (pintype "power_in"))
      (node (ref "U4") (pin "6") (pinfunction "QSTRT_6") (pintype "input"))
      (node (ref "U4") (pin "9") (pinfunction "EP_9") (pintype "power_in"))
    )
    (net (code "14") (name "GPIO8") (class "Default")
      (node (ref "R1") (pin "1") (pinfunction "1_1") (pintype "passive"))
      (node (ref "U2") (pin "10") (pinfunction "IO8_10") (pintype "bidirectional"))
    )
    (net (code "15") (name "I2C_PW") (class "Default")
      (node (ref "C1") (pin "1") (pinfunction "1_1") (pintype "passive"))
      (node (ref "C2") (pin "1") (pinfunction "1_1") (pintype "passive"))
      (node (ref "R1_PINH") (pin "2") (pinfunction "2_2") (pintype "passive"))
      (node (ref "R2-PINH") (pin "2") (pinfunction "2_2") (pintype "passive"))
      (node (ref "SENSOR2") (pin "2") (pinfunction "CSB_2") (pintype "input"))
      (node (ref "SENSOR2") (pin "6") (pinfunction "VDDIO_6") (pintype "power_in"))
      (node (ref "SENSOR2") (pin "8") (pinfunction "VDD_8") (pintype "power_in"))
      (node (ref "U2") (pin "17") (pinfunction "IO19_17") (pintype "bidirectional"))
    )
    (net (code "16") (name "INT_RTC") (class "Default")
      (node (ref "INT_RTC") (pin "TP") (pinfunction "TP_TP") (pintype "input"))
      (node (ref "R1_PINH1") (pin "1") (pinfunction "1_1") (pintype "passive"))
      (node (ref "U2") (pin "8") (pinfunction "IO0_8") (pintype "bidirectional"))
      (node (ref "U3") (pin "3") (pinfunction "SQW/~{INT}_3") (pintype "output"))
    )
    (net (code "17") (name "IO{slash}BOOT") (class "Default")
      (node (ref "BOOT_BUTTON") (pin "3") (pinfunction "3_3") (pintype "passive"))
      (node (ref "BOOT_BUTTON") (pin "4") (pinfunction "4_4") (pintype "passive"))
      (node (ref "C6") (pin "1") (pinfunction "1_1") (pintype "passive"))
      (node (ref "R_BOOT") (pin "1") (pinfunction "1_1") (pintype "passive"))
      (node (ref "U2") (pin "15") (pinfunction "IO9_15") (pintype "bidirectional"))
    )
    (net (code "18") (name "IO{slash}CHANGE") (class "Default")
      (node (ref "C10") (pin "1") (pinfunction "1_1") (pintype "passive"))
      (node (ref "CHANGE_BUTTON") (pin "3") (pinfunction "3_3") (pintype "passive"))
      (node (ref "CHANGE_BUTTON") (pin "4") (pinfunction "4_4") (pintype "passive"))
      (node (ref "R_CHANGE") (pin "1") (pinfunction "1_1") (pintype "passive"))
      (node (ref "U2") (pin "23") (pinfunction "IO15_23") (pintype "bidirectional"))
    )
    (net (code "19") (name "MISO") (class "Default")
      (node (ref "D12") (pin "2") (pinfunction "2_2") (pintype "passive"))
      (node (ref "J4") (pin "P7") (pinfunction "DAT0_P7") (pintype "bidirectional"))
      (node (ref "MISO") (pin "TP") (pinfunction "TP_TP") (pintype "input"))
      (node (ref "R8") (pin "1") (pinfunction "1_1") (pintype "passive"))
      (node (ref "U1") (pin "2") (pinfunction "DO(IO1)_2") (pintype "bidirectional"))
      (node (ref "U2") (pin "27") (pinfunction "IO2_27") (pintype "bidirectional"))
    )
    (net (code "20") (name "MOSI") (class "Default")
      (node (ref "D11") (pin "2") (pinfunction "2_2") (pintype "passive"))
      (node (ref "J1") (pin "14") (pinfunction "14_14") (pintype "bidirectional"))
      (node (ref "J4") (pin "P3") (pinfunction "CMD_P3") (pintype "bidirectional"))
      (node (ref "MOSI") (pin "TP") (pinfunction "TP_TP") (pintype "input"))
      (node (ref "R7") (pin "1") (pinfunction "1_1") (pintype "passive"))
      (node (ref "U1") (pin "5") (pinfunction "DI(IO0)_5") (pintype "bidirectional"))
      (node (ref "U2") (pin "7") (pinfunction "IO7_7") (pintype "bidirectional"))
    )
    (net (code "21") (name "Net-(CHG_LED-PadC)") (class "Default")
      (node (ref "CHG_LED") (pin "C") (pinfunction "C_C") (pintype "passive"))
      (node (ref "R1_BAT") (pin "1") (pinfunction "1_1") (pintype "passive"))
    )
    (net (code "22") (name "Net-(D2-CATHODE)") (class "Default")
      (node (ref "C1_BAT1") (pin "1") (pinfunction "1_1") (pintype "passive"))
      (node (ref "D2") (pin "1") (pinfunction "CATHODE_1") (pintype "bidirectional"))
      (node (ref "IC4") (pin "1") (pinfunction "VIN_1") (pintype "bidirectional"))
      (node (ref "IC4") (pin "3") (pinfunction "CE_3") (pintype "bidirectional"))
      (node (ref "Q1") (pin "2") (pinfunction "S_2") (pintype "bidirectional"))
    )
    (net (code "23") (name "Net-(D3-A)") (class "Default")
      (node (ref "C4") (pin "1") (pinfunction "1_1") (pintype "passive"))
      (node (ref "D3") (pin "2") (pinfunction "A_2") (pintype "bidirectional"))
      (node (ref "D4") (pin "1") (pinfunction "K_1") (pintype "bidirectional"))
    )
    (net (code "24") (name "Net-(D7-CATHODE)") (class "Default")
      (node (ref "D7") (pin "1") (pinfunction "CATHODE_1") (pintype "bidirectional"))
      (node (ref "R_CAPACITOR") (pin "1") (pinfunction "1_1") (pintype "passive"))
    )
    (net (code "25") (name "Net-(EPD_C1-Pad2)") (class "Default")
      (node (ref "EPD_C1") (pin "2") (pinfunction "2_2") (pintype "passive"))
      (node (ref "J1") (pin "4") (pinfunction "4_4") (pintype "bidirectional"))
    )
    (net (code "26") (name "Net-(EPD_C2-Pad2)") (class "Default")
      (node (ref "EPD_C2") (pin "2") (pinfunction "2_2") (pintype "passive"))
      (node (ref "J1") (pin "5") (pinfunction "5_5") (pintype "bidirectional"))
    )
    (net (code "27") (name "Net-(EPD_C6-Pad2)") (class "Default")
      (node (ref "EPD_C6") (pin "2") (pinfunction "2_2") (pintype "passive"))
      (node (ref "J1") (pin "18") (pinfunction "18_18") (pintype "bidirectional"))
    )
    (net (code "28") (name "Net-(EPD_C7-Pad2)") (class "Default")
      (node (ref "EPD_C7") (pin "2") (pinfunction "2_2") (pintype "passive"))
      (node (ref "J1") (pin "19") (pinfunction "19_19") (pintype "bidirectional"))
    )
    (net (code "29") (name "Net-(EPD_C8-Pad2)") (class "Default")
      (node (ref "EPD_C8") (pin "2") (pinfunction "2_2") (pintype "passive"))
      (node (ref "J1") (pin "20") (pinfunction "20_20") (pintype "bidirectional"))
    )
    (net (code "30") (name "Net-(EPD_C10-Pad2)") (class "Default")
      (node (ref "EPD_C10") (pin "2") (pinfunction "2_2") (pintype "passive"))
      (node (ref "J1") (pin "22") (pinfunction "22_22") (pintype "bidirectional"))
    )
    (net (code "31") (name "Net-(EPD_C12-Pad2)") (class "Default")
      (node (ref "EPD_C12") (pin "2") (pinfunction "2_2") (pintype "passive"))
      (node (ref "J1") (pin "24") (pinfunction "24_24") (pintype "bidirectional"))
    )
    (net (code "32") (name "Net-(IC1-CT)") (class "Default")
      (node (ref "C_DELAY") (pin "1") (pinfunction "1_1") (pintype "passive"))
      (node (ref "IC1") (pin "5") (pinfunction "CT_5") (pintype "bidirectional"))
    )
    (net (code "33") (name "Net-(J2-PadA5)") (class "Default")
      (node (ref "J2") (pin "A5") (pinfunction "A5_A5") (pintype "bidirectional"))
      (node (ref "R2-USB1") (pin "2") (pinfunction "2_2") (pintype "passive"))
    )
    (net (code "34") (name "Net-(J2-PadB5)") (class "Default")
      (node (ref "J2") (pin "B5") (pinfunction "B5_B5") (pintype "bidirectional"))
      (node (ref "R2-USB") (pin "1") (pinfunction "1_1") (pintype "passive"))
    )
    (net (code "35") (name "Net-(MCP73831-PROG)") (class "Default")
      (node (ref "MCP73831") (pin "5") (pinfunction "PROG_5") (pintype "input"))
      (node (ref "R2_BAT") (pin "2") (pinfunction "2_2") (pintype "passive"))
    )
    (net (code "36") (name "Net-(MCP73831-STAT)") (class "Default")
      (node (ref "MCP73831") (pin "1") (pinfunction "STAT_1") (pintype "output"))
      (node (ref "R1_BAT") (pin "2") (pinfunction "2_2") (pintype "passive"))
    )
    (net (code "37") (name "PREVGH") (class "Default")
      (node (ref "D5") (pin "1") (pinfunction "K_1") (pintype "bidirectional"))
      (node (ref "EPD_C9") (pin "2") (pinfunction "2_2") (pintype "passive"))
      (node (ref "J1") (pin "21") (pinfunction "21_21") (pintype "bidirectional"))
    )
    (net (code "38") (name "PREVGL") (class "Default")
      (node (ref "D4") (pin "2") (pinfunction "A_2") (pintype "bidirectional"))
      (node (ref "EPD_C11") (pin "2") (pinfunction "2_2") (pintype "passive"))
      (node (ref "J1") (pin "23") (pinfunction "23_23") (pintype "bidirectional"))
    )
    (net (code "39") (name "RESE") (class "Default")
      (node (ref "J1") (pin "3") (pinfunction "3_3") (pintype "bidirectional"))
      (node (ref "Q3") (pin "2") (pinfunction "S_2") (pintype "bidirectional"))
      (node (ref "R3") (pin "2") (pinfunction "2_2") (pintype "passive"))
    )
    (net (code "40") (name "RESE'") (class "Default")
      (node (ref "R2") (pin "2") (pinfunction "2_2") (pintype "passive"))
      (node (ref "R3") (pin "1") (pinfunction "1_1") (pintype "passive"))
      (node (ref "SJ1") (pin "2") (pinfunction "2_2") (pintype "passive"))
    )
    (net (code "41") (name "RESET") (class "Default")
      (node (ref "C5") (pin "1") (pinfunction "1_1") (pintype "passive"))
      (node (ref "IC1") (pin "1") (pinfunction "VOUT_1") (pintype "bidirectional"))
      (node (ref "RESET_BUTTON") (pin "3") (pinfunction "3_3") (pintype "passive"))
      (node (ref "RESET_BUTTON") (pin "4") (pinfunction "4_4") (pintype "passive"))
      (node (ref "R_RESET") (pin "1") (pinfunction "1_1") (pintype "passive"))
      (node (ref "U2") (pin "3") (pinfunction "EN_3") (pintype "input"))
    )
    (net (code "42") (name "RTC_RST") (class "Default")
      (node (ref "U2") (pin "16") (pinfunction "IO18_16") (pintype "bidirectional"))
      (node (ref "U3") (pin "4") (pinfunction "~{RST}_4") (pintype "input"))
    )
    (net (code "43") (name "RX") (class "Default")
      (node (ref "RX") (pin "TP") (pinfunction "TP_TP") (pintype "input"))
      (node (ref "U2") (pin "24") (pinfunction "RXD0/GPIO17_24") (pintype "bidirectional"))
    )
    (net (code "44") (name "SCK") (class "Default")
      (node (ref "D10") (pin "2") (pinfunction "2_2") (pintype "passive"))
      (node (ref "J1") (pin "13") (pinfunction "13_13") (pintype "bidirectional"))
      (node (ref "J4") (pin "P5") (pinfunction "CLK_P5") (pintype "bidirectional"))
      (node (ref "R6") (pin "1") (pinfunction "1_1") (pintype "passive"))
      (node (ref "SCK") (pin "TP") (pinfunction "TP_TP") (pintype "input"))
      (node (ref "U1") (pin "6") (pinfunction "CLK_6") (pintype "input"))
      (node (ref "U2") (pin "6") (pinfunction "IO6_6") (pintype "bidirectional"))
    )
    (net (code "45") (name "SCL") (class "Default")
      (node (ref "J3") (pin "4") (pinfunction "4_4") (pintype "passive"))
      (node (ref "R2-PINH") (pin "1") (pinfunction "1_1") (pintype "passive"))
      (node (ref "SENSOR2") (pin "4") (pinfunction "SCK_4") (pintype "input"))
      (node (ref "U2") (pin "20") (pinfunction "IO22_20") (pintype "bidirectional"))
      (node (ref "U3") (pin "16") (pinfunction "SCL_16") (pintype "input"))
      (node (ref "U4") (pin "7") (pinfunction "SCL_7") (pintype "input"))
    )
    (net (code "46") (name "SDA") (class "Default")
      (node (ref "J3") (pin "3") (pinfunction "3_3") (pintype "passive"))
      (node (ref "R1_PINH") (pin "1") (pinfunction "1_1") (pintype "passive"))
      (node (ref "SENSOR2") (pin "3") (pinfunction "SDI_3") (pintype "bidirectional"))
      (node (ref "U2") (pin "19") (pinfunction "IO21_19") (pintype "bidirectional"))
      (node (ref "U3") (pin "15") (pinfunction "SDA_15") (pintype "bidirectional"))
      (node (ref "U4") (pin "8") (pinfunction "SDA_8") (pintype "bidirectional"))
    )
    (net (code "47") (name "SRC") (class "Default")
      (node (ref "C4") (pin "2") (pinfunction "2_2") (pintype "passive"))
      (node (ref "D5") (pin "2") (pinfunction "A_2") (pintype "bidirectional"))
      (node (ref "L1") (pin "1") (pinfunction "1_1") (pintype "passive"))
      (node (ref "Q3") (pin "3") (pinfunction "D_3") (pintype "bidirectional"))
    )
    (net (code "48") (name "SS_SD") (class "Default")
      (node (ref "D8") (pin "2") (pinfunction "2_2") (pintype "passive"))
      (node (ref "J4") (pin "P2") (pinfunction "CD/DAT3_P2") (pintype "bidirectional"))
      (node (ref "R10") (pin "1") (pinfunction "1_1") (pintype "passive"))
      (node (ref "U2") (pin "4") (pinfunction "IO4_4") (pintype "bidirectional"))
    )
    (net (code "49") (name "TX") (class "Default")
      (node (ref "TX") (pin "TP") (pinfunction "TP_TP") (pintype "input"))
      (node (ref "U2") (pin "25") (pinfunction "TXD0/GPIO16_25") (pintype "bidirectional"))
    )
    (net (code "50") (name "USB_D+") (class "Default")
      (node (ref "D1") (pin "1") (pinfunction "I/O1_1_1") (pintype "bidirectional"))
      (node (ref "U2") (pin "14") (pinfunction "IO13_14") (pintype "bidirectional"))
    )
    (net (code "51") (name "USB_D-") (class "Default")
      (node (ref "D1") (pin "3") (pinfunction "I/O2_1_3") (pintype "bidirectional"))
      (node (ref "U2") (pin "13") (pinfunction "IO12_13") (pintype "bidirectional"))
    )
    (net (code "52") (name "VBAT") (class "Default")
      (node (ref "C2_BAT") (pin "1") (pinfunction "1_1") (pintype "passive"))
      (node (ref "MCP73831") (pin "3") (pinfunction "VBAT_3") (pintype "power_in"))
      (node (ref "Q1") (pin "3") (pinfunction "D_3") (pintype "bidirectional"))
      (node (ref "U4") (pin "2") (pinfunction "CELL_2") (pintype "power_in"))
      (node (ref "U4") (pin "3") (pinfunction "VDD_3") (pintype "power_in"))
      (node (ref "VBAT") (pin "TP") (pinfunction "TP_TP") (pintype "input"))
    )
    (net (code "53") (name "VBUS") (class "Default")
      (node (ref "C1_BAT") (pin "1") (pinfunction "1_1") (pintype "passive"))
      (node (ref "C4_USB") (pin "1") (pinfunction "1_1") (pintype "passive"))
      (node (ref "C5_USB") (pin "1") (pinfunction "1_1") (pintype "passive"))
      (node (ref "CHG_LED") (pin "A") (pinfunction "A_A") (pintype "passive"))
      (node (ref "D1") (pin "5") (pinfunction "VBUS_5") (pintype "bidirectional"))
      (node (ref "D2") (pin "2") (pinfunction "ANODE_2") (pintype "bidirectional"))
      (node (ref "MCP73831") (pin "4") (pinfunction "VIN_4") (pintype "power_in"))
      (node (ref "PFMF.050.1") (pin "2") (pinfunction "2_2") (pintype "passive"))
      (node (ref "Q1") (pin "1") (pinfunction "G_1") (pintype "bidirectional"))
      (node (ref "R1_PWRUSB") (pin "1") (pinfunction "1_1") (pintype "passive"))
      (node (ref "VBUS") (pin "TP") (pinfunction "TP_TP") (pintype "input"))
    )
    (net (code "54") (name "VRTC") (class "Default")
      (node (ref "C10_SUPERCAP") (pin "1") (pinfunction "1_1") (pintype "passive"))
      (node (ref "C8") (pin "1") (pinfunction "1_1") (pintype "passive"))
      (node (ref "R_CAPACITOR") (pin "2") (pinfunction "2_2") (pintype "passive"))
      (node (ref "U3") (pin "14") (pinfunction "VBAT_14") (pintype "power_in"))
    )
    (net (code "55") (name "VUSB") (class "Default")
      (node (ref "J2") (pin "A4") (pinfunction "A4_A4") (pintype "bidirectional"))
      (node (ref "J2") (pin "A9") (pinfunction "A9_A9") (pintype "bidirectional"))
      (node (ref "J2") (pin "B4") (pinfunction "B4_B4") (pintype "bidirectional"))
      (node (ref "J2") (pin "B9") (pinfunction "B9_B9") (pintype "bidirectional"))
      (node (ref "PFMF.050.1") (pin "1") (pinfunction "1_1") (pintype "passive"))
    )
    (net (code "56") (name "unconnected-(IC1-NC-Pad4)") (class "Default")
      (node (ref "IC1") (pin "4") (pinfunction "NC_4") (pintype "no_connect"))
    )
    (net (code "57") (name "unconnected-(IC4-NC-Pad4)") (class "Default")
      (node (ref "IC4") (pin "4") (pinfunction "NC_4") (pintype "no_connect"))
    )
    (net (code "58") (name "unconnected-(J1-Pad1)") (class "Default")
      (node (ref "J1") (pin "1") (pinfunction "1_1") (pintype "bidirectional"))
    )
    (net (code "59") (name "unconnected-(J1-Pad6)") (class "Default")
      (node (ref "J1") (pin "6") (pinfunction "6_6") (pintype "bidirectional"))
    )
    (net (code "60") (name "unconnected-(J1-Pad7)") (class "Default")
      (node (ref "J1") (pin "7") (pinfunction "7_7") (pintype "bidirectional"))
    )
    (net (code "61") (name "unconnected-(J2-PadA8)") (class "Default")
      (node (ref "J2") (pin "A8") (pinfunction "A8_A8") (pintype "bidirectional"))
    )
    (net (code "62") (name "unconnected-(J2-PadB8)") (class "Default")
      (node (ref "J2") (pin "B8") (pinfunction "B8_B8") (pintype "bidirectional"))
    )
    (net (code "63") (name "unconnected-(J4-DAT1-PadP8)") (class "Default")
      (node (ref "J4") (pin "P8") (pinfunction "DAT1_P8") (pintype "bidirectional"))
    )
    (net (code "64") (name "unconnected-(J4-DAT2-PadP1)") (class "Default")
      (node (ref "J4") (pin "P1") (pinfunction "DAT2_P1") (pintype "bidirectional"))
    )
    (net (code "65") (name "unconnected-(J4-DETECTION_1-PadS1)") (class "Default")
      (node (ref "J4") (pin "S1") (pinfunction "DETECTION_1_S1") (pintype "bidirectional"))
    )
    (net (code "66") (name "unconnected-(J4-DETECTION_2-PadS2)") (class "Default")
      (node (ref "J4") (pin "S2") (pinfunction "DETECTION_2_S2") (pintype "bidirectional"))
    )
    (net (code "67") (name "unconnected-(U2-NC-Pad22)") (class "Default")
      (node (ref "U2") (pin "22") (pinfunction "NC_22") (pintype "no_connect"))
    )
    (net (code "68") (name "unconnected-(U4-~{ALERT}-Pad5)") (class "Default")
      (node (ref "U4") (pin "5") (pinfunction "~{ALERT}_5") (pintype "output"))
    )
  )
)
